# Board2.net
KiCad netlist of a schematic drawn in EasyEDA Pro
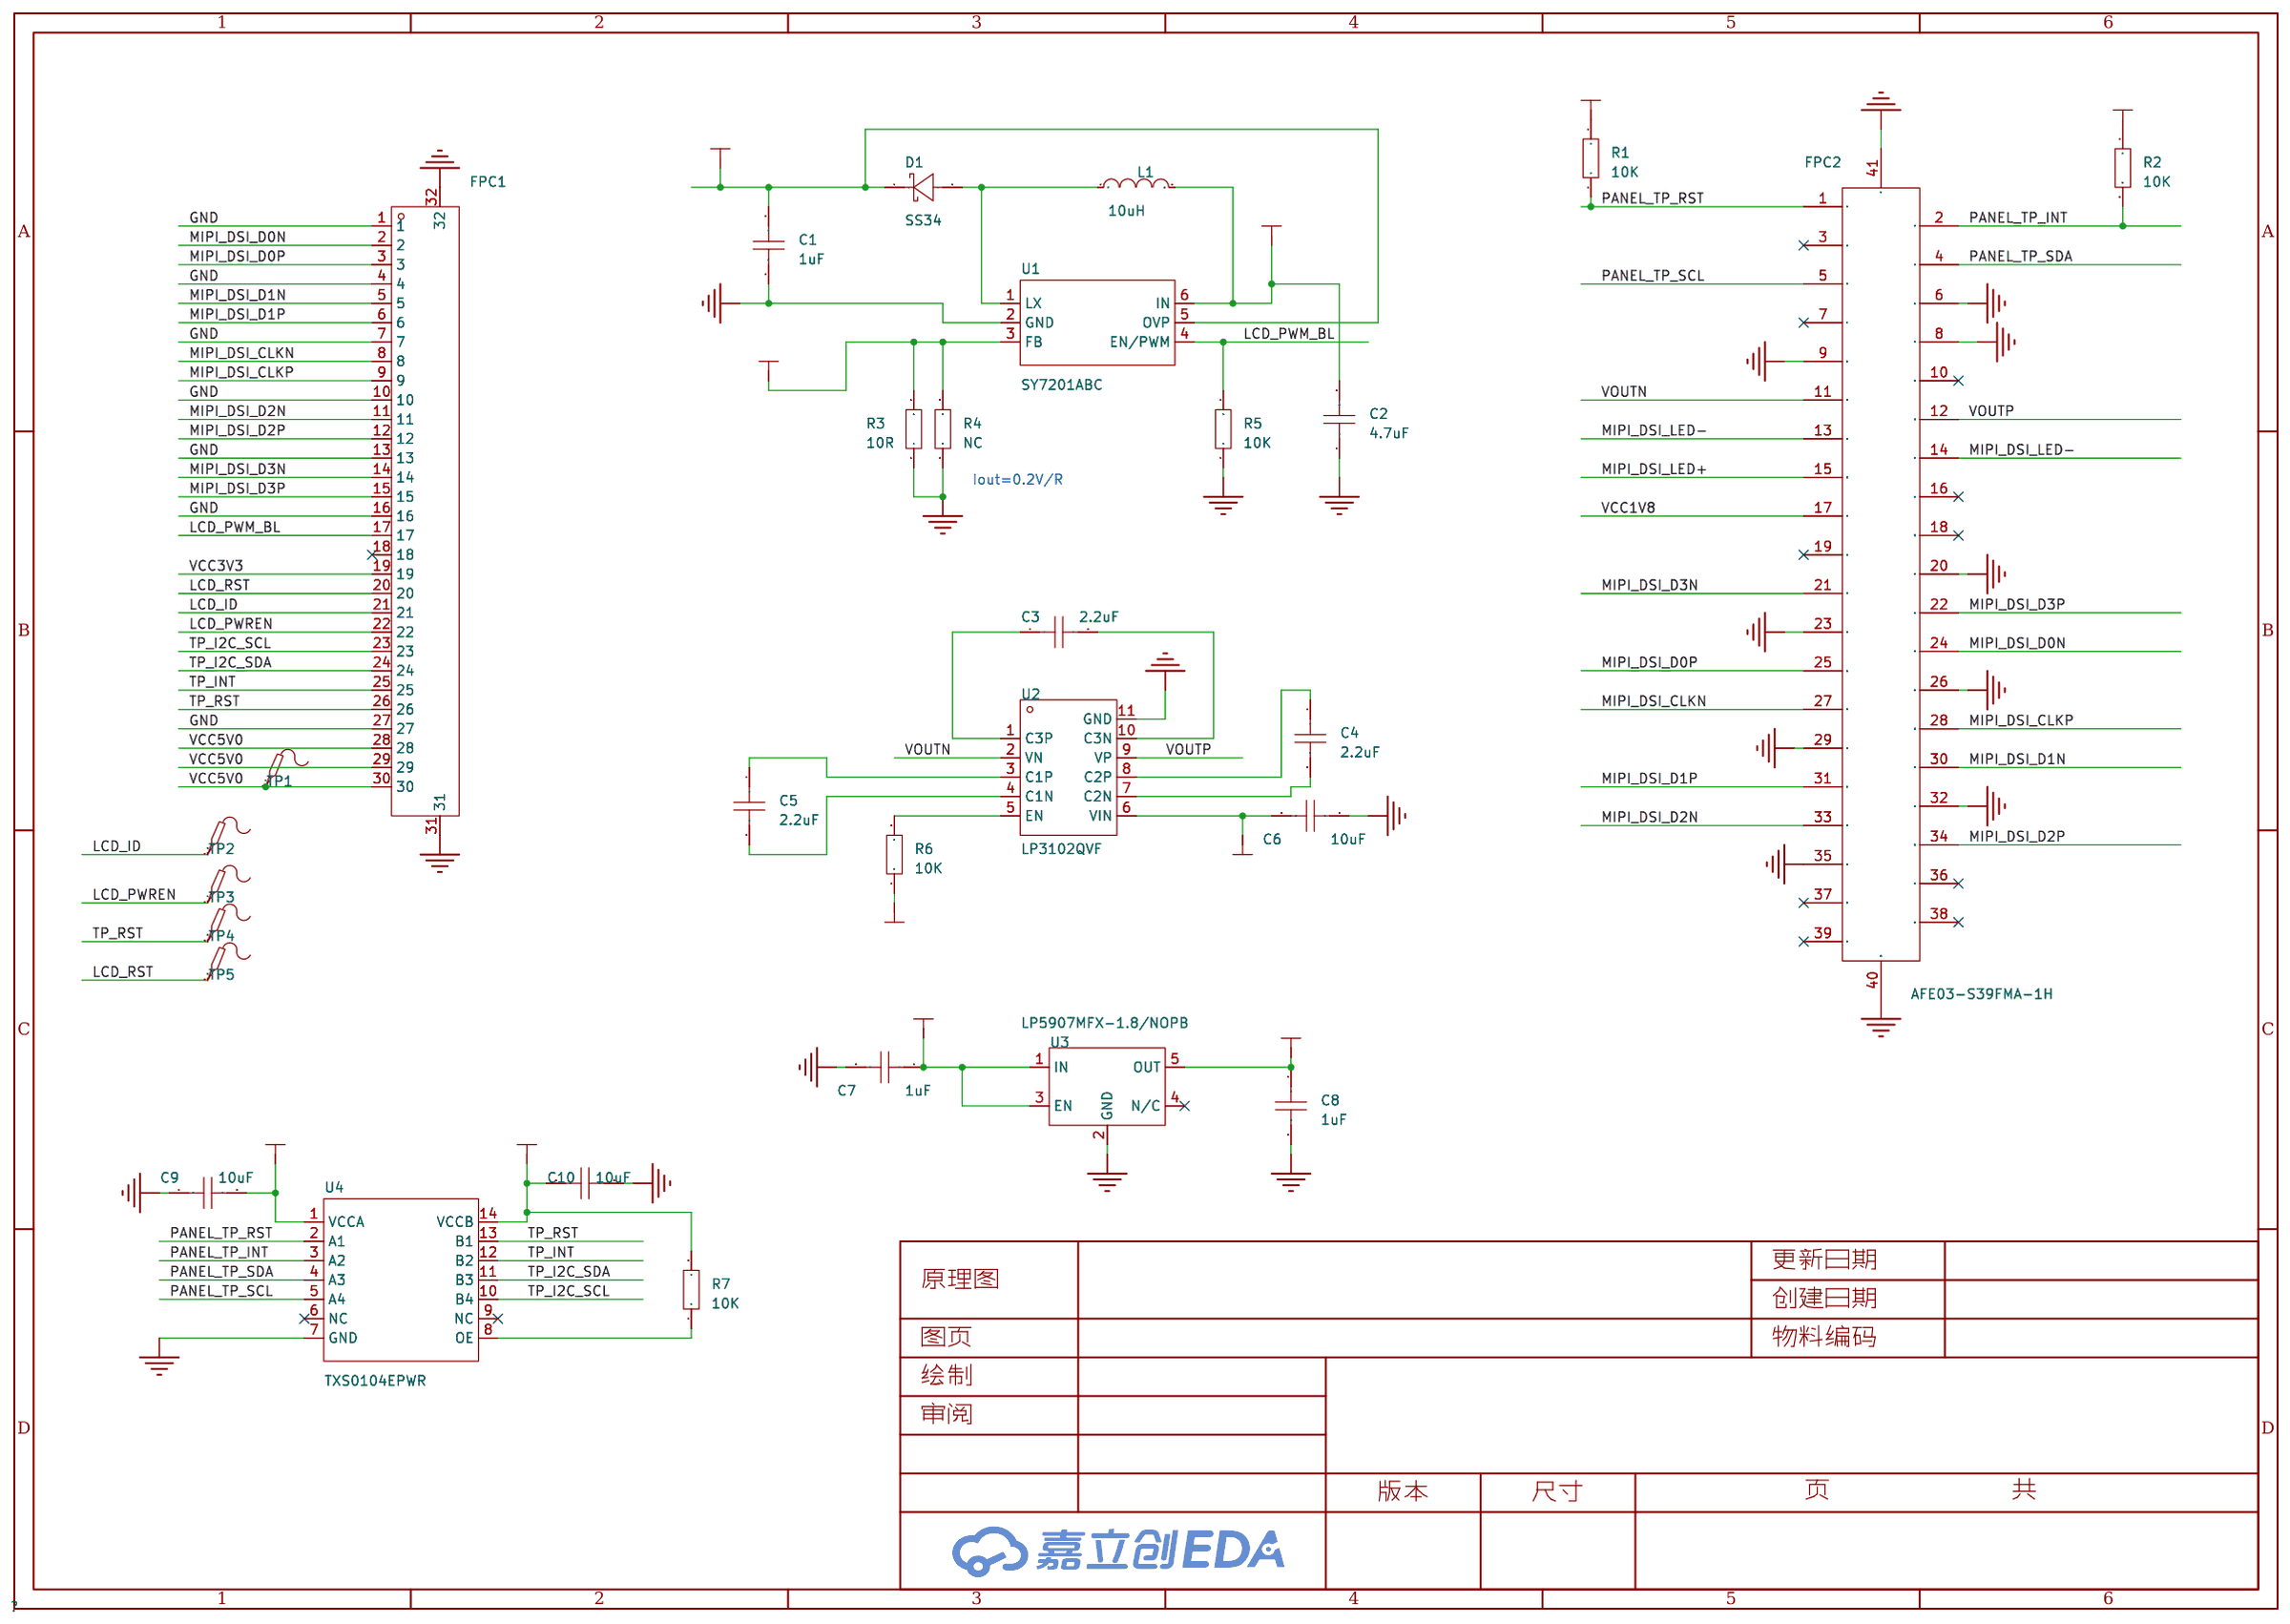
[diagram p0: schematic sheet]

(export (version "E")
  (design (tool "Eeschema 10.0.6"))
  (components
    (comp (ref "C1")
      (value "1uF")
      (footprint "easyedapro:C0603")
      (libsource (lib "easyedapro") (part "CapAcitance"))
    )
    (comp (ref "C2")
      (value "4.7uF")
      (footprint "easyedapro:C0603")
      (libsource (lib "easyedapro") (part "CapAcitance"))
    )
    (comp (ref "C3")
      (value "2.2uF")
      (footprint "easyedapro:C0603")
      (libsource (lib "easyedapro") (part "CapAcitance"))
    )
    (comp (ref "C4")
      (value "2.2uF")
      (footprint "easyedapro:C0603")
      (libsource (lib "easyedapro") (part "CapAcitance"))
    )
    (comp (ref "C5")
      (value "2.2uF")
      (footprint "easyedapro:C0603")
      (libsource (lib "easyedapro") (part "CapAcitance"))
    )
    (comp (ref "C6")
      (value "10uF")
      (footprint "easyedapro:C0603")
      (libsource (lib "easyedapro") (part "CapAcitance"))
    )
    (comp (ref "C7")
      (value "1uF")
      (footprint "easyedapro:C0603")
      (libsource (lib "easyedapro") (part "CapAcitance"))
    )
    (comp (ref "C8")
      (value "1uF")
      (footprint "easyedapro:C0603")
      (libsource (lib "easyedapro") (part "CapAcitance"))
    )
    (comp (ref "C9")
      (value "10uF")
      (footprint "easyedapro:C0603")
      (libsource (lib "easyedapro") (part "CapAcitance"))
    )
    (comp (ref "C10")
      (value "10uF")
      (footprint "easyedapro:C0603")
      (libsource (lib "easyedapro") (part "CapAcitance"))
    )
    (comp (ref "D1")
      (value "SS34")
      (footprint "easyedapro:SMA_L4.2-W2.7-LS5.0-RD")
      (description "二极管配置:-;正向压降(Vf):550mV@3A;直流反向耐压(Vr):40V;整流电流:3A;")
      (fields (field (name "Manufacturer") "JSMSEMI(杰盛微)"))
      (libsource (lib "easyedapro") (part "SS34_C2837271"))
    )
    (comp (ref "FPC1")
      (value "FPC-05F-30PH20")
      (footprint "easyedapro:FPC-SMD_30P-P0.50_XUNPU_FPC-05F-30PH20")
      (description "锁定特性:翻盖式;触点类型:卧贴;触点数量:30P;间距:0.5mm;安装方式:下接;工作温度:-25°C~+85°C;")
      (fields (field (name "Manufacturer") "XUNPU(讯普)"))
      (libsource (lib "easyedapro") (part "FPC-05F-30PH20"))
    )
    (comp (ref "FPC2")
      (value "AFE03-S39FMA-1H")
      (footprint "easyedapro:FPC-SMD_P0.30-39P_FGS-XJ-H1.0")
      (description "锁定特性:翻盖式;触点类型:下接;触点数量:39P;间距:0.3mm;安装方式:卧贴;")
      (fields (field (name "Manufacturer") "JS(钜硕电子)"))
      (libsource (lib "easyedapro") (part "AFE03-S39FMA-1H"))
    )
    (comp (ref "L1")
      (value "10uH")
      (footprint "easyedapro:L0603")
      (description "电感值:10uH;精度:±20%;额定电流:50mA;饱和电流(Isat):50mA;直流电阻(DCR):1.17Ω;")
      (fields (field (name "Manufacturer Part") "LQM18FN100M00D") (field (name "Manufacturer") "muRata(村田)"))
      (libsource (lib "easyedapro") (part "LQM18FN100M00D"))
    )
    (comp (ref "R1") (value "10K") (footprint "easyedapro:R0603") (libsource (lib "easyedapro") (part "电阻")))
    (comp (ref "R2") (value "10K") (footprint "easyedapro:R0603") (libsource (lib "easyedapro") (part "电阻")))
    (comp (ref "R3") (value "10R") (footprint "easyedapro:R0603") (libsource (lib "easyedapro") (part "电阻")))
    (comp (ref "R4") (value "NC") (footprint "easyedapro:R0603") (libsource (lib "easyedapro") (part "电阻")))
    (comp (ref "R5") (value "10K") (footprint "easyedapro:R0603") (libsource (lib "easyedapro") (part "电阻")))
    (comp (ref "R6") (value "10K") (footprint "easyedapro:R0603") (libsource (lib "easyedapro") (part "电阻")))
    (comp (ref "R7") (value "10K") (footprint "easyedapro:R0603") (libsource (lib "easyedapro") (part "电阻")))
    (comp (ref "TP1")
      (value "~")
      (footprint "easyedapro:Test-Point-0.5mm")
      (description "Test Point 测试点")
      (libsource (lib "easyedapro") (part "Test-Point"))
    )
    (comp (ref "TP2")
      (value "~")
      (footprint "easyedapro:Test-Point-0.5mm")
      (description "Test Point 测试点")
      (libsource (lib "easyedapro") (part "Test-Point"))
    )
    (comp (ref "TP3")
      (value "~")
      (footprint "easyedapro:Test-Point-0.5mm")
      (description "Test Point 测试点")
      (libsource (lib "easyedapro") (part "Test-Point"))
    )
    (comp (ref "TP4")
      (value "~")
      (footprint "easyedapro:Test-Point-0.5mm")
      (description "Test Point 测试点")
      (libsource (lib "easyedapro") (part "Test-Point"))
    )
    (comp (ref "TP5")
      (value "~")
      (footprint "easyedapro:Test-Point-0.5mm")
      (description "Test Point 测试点")
      (libsource (lib "easyedapro") (part "Test-Point"))
    )
    (comp (ref "U1")
      (value "SY7201ABC")
      (footprint "easyedapro:SOT-23-6_L2.9-W1.6-P0.95-LS2.8-BR")
      (description "类型:DC-DC;工作电压(DC):2.5V~30V;开关频率:1MHz;通道数:-;输出电压:-;输出电流:-;调光:PWM;拓扑结构:升压;")
      (fields (field (name "Manufacturer") "Silergy(矽力杰)"))
      (libsource (lib "easyedapro") (part "SY7201ABC"))
    )
    (comp (ref "U2")
      (value "LP3102QVF")
      (footprint "easyedapro:TDFN-10_L3.0-W3.0-P0.50-BL-EP")
      (fields (field (name "Manufacturer") "LOWPOWER(微源半导体)"))
      (libsource (lib "easyedapro") (part "LP3102QVF"))
    )
    (comp (ref "U3")
      (value "LP5907MFX-1.8/NOPB")
      (footprint "easyedapro:SOT-23-5_L3.0-W1.7-P0.95-LS2.8-BR")
      (description "输出类型:固定;工作电压:5.5V;输出电压:1.8V;输出电流:250mA;电源纹波抑制比(PSRR):82dB@(1kHz);输出极性:正极;")
      (fields (field (name "Manufacturer") "TI(德州仪器)"))
      (libsource (lib "easyedapro") (part "LP5907MFX-1.8/NOPB"))
    )
    (comp (ref "U4")
      (value "TXS0104EPWR")
      (footprint "easyedapro:TSSOP-14_L5.0-W4.4-P0.65-LS6.4-BL")
      (description "数据速率:24Mbps;工作电压(VCCA):1.65V~3.6V;工作电压(VCCB):2.3V~5.5V;元件数:1;每个电路通道数:4;")
      (fields (field (name "Manufacturer") "TI(德州仪器)"))
      (libsource (lib "easyedapro") (part "TXS0104EPWR"))
    )
  )
  (nets
    (net (code "1") (name "/LCD_ID") (class "Default")
      (node (ref "FPC1") (pin "21") (pinfunction "21_21") (pintype "unspecified"))
      (node (ref "TP2") (pin "1") (pinfunction "1_1") (pintype "input"))
    )
    (net (code "2") (name "/LCD_PWM_BL") (class "Default")
      (node (ref "FPC1") (pin "17") (pinfunction "17_17") (pintype "unspecified"))
      (node (ref "R5") (pin "2") (pinfunction "2_2") (pintype "input"))
      (node (ref "U1") (pin "4") (pinfunction "EN/PWM_4") (pintype "unspecified"))
    )
    (net (code "3") (name "/LCD_PWREN") (class "Default")
      (node (ref "FPC1") (pin "22") (pinfunction "22_22") (pintype "unspecified"))
      (node (ref "TP3") (pin "1") (pinfunction "1_1") (pintype "input"))
    )
    (net (code "4") (name "/LCD_RST") (class "Default")
      (node (ref "FPC1") (pin "20") (pinfunction "20_20") (pintype "unspecified"))
      (node (ref "TP5") (pin "1") (pinfunction "1_1") (pintype "input"))
    )
    (net (code "5") (name "/MIPI_DSI_CLKN") (class "Default")
      (node (ref "FPC1") (pin "8") (pinfunction "8_8") (pintype "unspecified"))
      (node (ref "FPC2") (pin "27") (pinfunction "27_27") (pintype "unspecified"))
    )
    (net (code "6") (name "/MIPI_DSI_CLKP") (class "Default")
      (node (ref "FPC1") (pin "9") (pinfunction "9_9") (pintype "unspecified"))
      (node (ref "FPC2") (pin "28") (pinfunction "28_28") (pintype "unspecified"))
    )
    (net (code "7") (name "/MIPI_DSI_D0N") (class "Default")
      (node (ref "FPC1") (pin "2") (pinfunction "2_2") (pintype "unspecified"))
      (node (ref "FPC2") (pin "24") (pinfunction "24_24") (pintype "unspecified"))
    )
    (net (code "8") (name "/MIPI_DSI_D0P") (class "Default")
      (node (ref "FPC1") (pin "3") (pinfunction "3_3") (pintype "unspecified"))
      (node (ref "FPC2") (pin "25") (pinfunction "25_25") (pintype "unspecified"))
    )
    (net (code "9") (name "/MIPI_DSI_D1N") (class "Default")
      (node (ref "FPC1") (pin "5") (pinfunction "5_5") (pintype "unspecified"))
      (node (ref "FPC2") (pin "30") (pinfunction "30_30") (pintype "unspecified"))
    )
    (net (code "10") (name "/MIPI_DSI_D1P") (class "Default")
      (node (ref "FPC1") (pin "6") (pinfunction "6_6") (pintype "unspecified"))
      (node (ref "FPC2") (pin "31") (pinfunction "31_31") (pintype "unspecified"))
    )
    (net (code "11") (name "/MIPI_DSI_D2N") (class "Default")
      (node (ref "FPC1") (pin "11") (pinfunction "11_11") (pintype "unspecified"))
      (node (ref "FPC2") (pin "33") (pinfunction "33_33") (pintype "unspecified"))
    )
    (net (code "12") (name "/MIPI_DSI_D2P") (class "Default")
      (node (ref "FPC1") (pin "12") (pinfunction "12_12") (pintype "unspecified"))
      (node (ref "FPC2") (pin "34") (pinfunction "34_34") (pintype "unspecified"))
    )
    (net (code "13") (name "/MIPI_DSI_D3N") (class "Default")
      (node (ref "FPC1") (pin "14") (pinfunction "14_14") (pintype "unspecified"))
      (node (ref "FPC2") (pin "21") (pinfunction "21_21") (pintype "unspecified"))
    )
    (net (code "14") (name "/MIPI_DSI_D3P") (class "Default")
      (node (ref "FPC1") (pin "15") (pinfunction "15_15") (pintype "unspecified"))
      (node (ref "FPC2") (pin "22") (pinfunction "22_22") (pintype "unspecified"))
    )
    (net (code "15") (name "/PANEL_TP_INT") (class "Default")
      (node (ref "FPC2") (pin "2") (pinfunction "2_2") (pintype "unspecified"))
      (node (ref "R2") (pin "2") (pinfunction "2_2") (pintype "input"))
      (node (ref "U4") (pin "3") (pinfunction "A2_3") (pintype "unspecified"))
    )
    (net (code "16") (name "/PANEL_TP_RST") (class "Default")
      (node (ref "FPC2") (pin "1") (pinfunction "1_1") (pintype "unspecified"))
      (node (ref "R1") (pin "2") (pinfunction "2_2") (pintype "input"))
      (node (ref "U4") (pin "2") (pinfunction "A1_2") (pintype "unspecified"))
    )
    (net (code "17") (name "/PANEL_TP_SCL") (class "Default")
      (node (ref "FPC2") (pin "5") (pinfunction "5_5") (pintype "unspecified"))
      (node (ref "U4") (pin "5") (pinfunction "A4_5") (pintype "unspecified"))
    )
    (net (code "18") (name "/PANEL_TP_SDA") (class "Default")
      (node (ref "FPC2") (pin "4") (pinfunction "4_4") (pintype "unspecified"))
      (node (ref "U4") (pin "4") (pinfunction "A3_4") (pintype "unspecified"))
    )
    (net (code "19") (name "/TP_I2C_SCL") (class "Default")
      (node (ref "FPC1") (pin "23") (pinfunction "23_23") (pintype "unspecified"))
      (node (ref "U4") (pin "10") (pinfunction "B4_10") (pintype "unspecified"))
    )
    (net (code "20") (name "/TP_I2C_SDA") (class "Default")
      (node (ref "FPC1") (pin "24") (pinfunction "24_24") (pintype "unspecified"))
      (node (ref "U4") (pin "11") (pinfunction "B3_11") (pintype "unspecified"))
    )
    (net (code "21") (name "/TP_INT") (class "Default")
      (node (ref "FPC1") (pin "25") (pinfunction "25_25") (pintype "unspecified"))
      (node (ref "U4") (pin "12") (pinfunction "B2_12") (pintype "unspecified"))
    )
    (net (code "22") (name "/TP_RST") (class "Default")
      (node (ref "FPC1") (pin "26") (pinfunction "26_26") (pintype "unspecified"))
      (node (ref "TP4") (pin "1") (pinfunction "1_1") (pintype "input"))
      (node (ref "U4") (pin "13") (pinfunction "B1_13") (pintype "unspecified"))
    )
    (net (code "23") (name "/VOUTN") (class "Default")
      (node (ref "FPC2") (pin "11") (pinfunction "11_11") (pintype "unspecified"))
      (node (ref "U2") (pin "2") (pinfunction "VN_2") (pintype "unspecified"))
    )
    (net (code "24") (name "/VOUTP") (class "Default")
      (node (ref "FPC2") (pin "12") (pinfunction "12_12") (pintype "unspecified"))
      (node (ref "U2") (pin "9") (pinfunction "VP_9") (pintype "unspecified"))
    )
    (net (code "25") (name "GND") (class "Default")
      (node (ref "C1") (pin "1") (pinfunction "1_1") (pintype "input"))
      (node (ref "C10") (pin "1") (pinfunction "1_1") (pintype "input"))
      (node (ref "C2") (pin "1") (pinfunction "1_1") (pintype "input"))
      (node (ref "C6") (pin "1") (pinfunction "1_1") (pintype "input"))
      (node (ref "C7") (pin "2") (pinfunction "2_2") (pintype "input"))
      (node (ref "C8") (pin "2") (pinfunction "2_2") (pintype "input"))
      (node (ref "C9") (pin "1") (pinfunction "1_1") (pintype "input"))
      (node (ref "FPC1") (pin "1") (pinfunction "1_1") (pintype "unspecified"))
      (node (ref "FPC1") (pin "10") (pinfunction "10_10") (pintype "unspecified"))
      (node (ref "FPC1") (pin "13") (pinfunction "13_13") (pintype "unspecified"))
      (node (ref "FPC1") (pin "16") (pinfunction "16_16") (pintype "unspecified"))
      (node (ref "FPC1") (pin "27") (pinfunction "27_27") (pintype "unspecified"))
      (node (ref "FPC1") (pin "31") (pinfunction "31_31") (pintype "unspecified"))
      (node (ref "FPC1") (pin "32") (pinfunction "32_32") (pintype "unspecified"))
      (node (ref "FPC1") (pin "4") (pinfunction "4_4") (pintype "unspecified"))
      (node (ref "FPC1") (pin "7") (pinfunction "7_7") (pintype "unspecified"))
      (node (ref "FPC2") (pin "20") (pinfunction "20_20") (pintype "unspecified"))
      (node (ref "FPC2") (pin "23") (pinfunction "23_23") (pintype "unspecified"))
      (node (ref "FPC2") (pin "26") (pinfunction "26_26") (pintype "unspecified"))
      (node (ref "FPC2") (pin "29") (pinfunction "29_29") (pintype "unspecified"))
      (node (ref "FPC2") (pin "32") (pinfunction "32_32") (pintype "unspecified"))
      (node (ref "FPC2") (pin "35") (pinfunction "35_35") (pintype "unspecified"))
      (node (ref "FPC2") (pin "40") (pinfunction "40_40") (pintype "unspecified"))
      (node (ref "FPC2") (pin "41") (pinfunction "41_41") (pintype "unspecified"))
      (node (ref "FPC2") (pin "6") (pinfunction "6_6") (pintype "unspecified"))
      (node (ref "FPC2") (pin "8") (pinfunction "8_8") (pintype "unspecified"))
      (node (ref "FPC2") (pin "9") (pinfunction "9_9") (pintype "unspecified"))
      (node (ref "R3") (pin "1") (pinfunction "1_1") (pintype "input"))
      (node (ref "R4") (pin "1") (pinfunction "1_1") (pintype "input"))
      (node (ref "R5") (pin "1") (pinfunction "1_1") (pintype "input"))
      (node (ref "U1") (pin "2") (pinfunction "GND_2") (pintype "unspecified"))
      (node (ref "U2") (pin "11") (pinfunction "GND_11") (pintype "unspecified"))
      (node (ref "U3") (pin "2") (pinfunction "GND_2") (pintype "unspecified"))
      (node (ref "U4") (pin "7") (pinfunction "GND_7") (pintype "unspecified"))
    )
    (net (code "26") (name "MIPI_DSI_LED+") (class "Default")
      (node (ref "C1") (pin "2") (pinfunction "2_2") (pintype "input"))
      (node (ref "D1") (pin "1") (pinfunction "K_1") (pintype "unspecified"))
      (node (ref "FPC2") (pin "15") (pinfunction "15_15") (pintype "unspecified"))
      (node (ref "U1") (pin "5") (pinfunction "OVP_5") (pintype "unspecified"))
    )
    (net (code "27") (name "MIPI_DSI_LED-") (class "Default")
      (node (ref "FPC2") (pin "13") (pinfunction "13_13") (pintype "unspecified"))
      (node (ref "FPC2") (pin "14") (pinfunction "14_14") (pintype "unspecified"))
      (node (ref "R3") (pin "2") (pinfunction "2_2") (pintype "input"))
      (node (ref "R4") (pin "2") (pinfunction "2_2") (pintype "input"))
      (node (ref "U1") (pin "3") (pinfunction "FB_3") (pintype "unspecified"))
    )
    (net (code "28") (name "Net-(D1-A)") (class "Default")
      (node (ref "D1") (pin "2") (pinfunction "A_2") (pintype "unspecified"))
      (node (ref "L1") (pin "1") (pinfunction "1_1") (pintype "unspecified"))
      (node (ref "U1") (pin "1") (pinfunction "LX_1") (pintype "unspecified"))
    )
    (net (code "29") (name "Net-(U2-C1N)") (class "Default")
      (node (ref "C5") (pin "2") (pinfunction "2_2") (pintype "input"))
      (node (ref "U2") (pin "4") (pinfunction "C1N_4") (pintype "unspecified"))
    )
    (net (code "30") (name "Net-(U2-C1P)") (class "Default")
      (node (ref "C5") (pin "1") (pinfunction "1_1") (pintype "input"))
      (node (ref "U2") (pin "3") (pinfunction "C1P_3") (pintype "unspecified"))
    )
    (net (code "31") (name "Net-(U2-C2N)") (class "Default")
      (node (ref "C4") (pin "2") (pinfunction "2_2") (pintype "input"))
      (node (ref "U2") (pin "7") (pinfunction "C2N_7") (pintype "unspecified"))
    )
    (net (code "32") (name "Net-(U2-C2P)") (class "Default")
      (node (ref "C4") (pin "1") (pinfunction "1_1") (pintype "input"))
      (node (ref "U2") (pin "8") (pinfunction "C2P_8") (pintype "unspecified"))
    )
    (net (code "33") (name "Net-(U2-C3N)") (class "Default")
      (node (ref "C3") (pin "2") (pinfunction "2_2") (pintype "input"))
      (node (ref "U2") (pin "10") (pinfunction "C3N_10") (pintype "unspecified"))
    )
    (net (code "34") (name "Net-(U2-C3P)") (class "Default")
      (node (ref "C3") (pin "1") (pinfunction "1_1") (pintype "input"))
      (node (ref "U2") (pin "1") (pinfunction "C3P_1") (pintype "unspecified"))
    )
    (net (code "35") (name "Net-(U2-EN)") (class "Default")
      (node (ref "R6") (pin "2") (pinfunction "2_2") (pintype "input"))
      (node (ref "U2") (pin "5") (pinfunction "EN_5") (pintype "unspecified"))
    )
    (net (code "36") (name "Net-(U4-OE)") (class "Default")
      (node (ref "R7") (pin "1") (pinfunction "1_1") (pintype "input"))
      (node (ref "U4") (pin "8") (pinfunction "OE_8") (pintype "unspecified"))
    )
    (net (code "37") (name "VCC1V8") (class "Default")
      (node (ref "C8") (pin "1") (pinfunction "1_1") (pintype "input"))
      (node (ref "C9") (pin "2") (pinfunction "2_2") (pintype "input"))
      (node (ref "FPC2") (pin "17") (pinfunction "17_17") (pintype "unspecified"))
      (node (ref "R1") (pin "1") (pinfunction "1_1") (pintype "input"))
      (node (ref "R2") (pin "1") (pinfunction "1_1") (pintype "input"))
      (node (ref "U3") (pin "5") (pinfunction "OUT_5") (pintype "unspecified"))
      (node (ref "U4") (pin "1") (pinfunction "VCCA_1") (pintype "unspecified"))
    )
    (net (code "38") (name "VCC3V3") (class "Default")
      (node (ref "C10") (pin "2") (pinfunction "2_2") (pintype "input"))
      (node (ref "C6") (pin "2") (pinfunction "2_2") (pintype "input"))
      (node (ref "FPC1") (pin "19") (pinfunction "19_19") (pintype "unspecified"))
      (node (ref "R6") (pin "1") (pinfunction "1_1") (pintype "input"))
      (node (ref "R7") (pin "2") (pinfunction "2_2") (pintype "input"))
      (node (ref "U2") (pin "6") (pinfunction "VIN_6") (pintype "unspecified"))
      (node (ref "U4") (pin "14") (pinfunction "VCCB_14") (pintype "unspecified"))
    )
    (net (code "39") (name "VCC5V0") (class "Default")
      (node (ref "C2") (pin "2") (pinfunction "2_2") (pintype "input"))
      (node (ref "C7") (pin "1") (pinfunction "1_1") (pintype "input"))
      (node (ref "FPC1") (pin "28") (pinfunction "28_28") (pintype "unspecified"))
      (node (ref "FPC1") (pin "29") (pinfunction "29_29") (pintype "unspecified"))
      (node (ref "FPC1") (pin "30") (pinfunction "30_30") (pintype "unspecified"))
      (node (ref "L1") (pin "2") (pinfunction "2_2") (pintype "unspecified"))
      (node (ref "TP1") (pin "1") (pinfunction "1_1") (pintype "input"))
      (node (ref "U1") (pin "6") (pinfunction "IN_6") (pintype "unspecified"))
      (node (ref "U3") (pin "1") (pinfunction "IN_1") (pintype "unspecified"))
      (node (ref "U3") (pin "3") (pinfunction "EN_3") (pintype "unspecified"))
    )
    (net (code "40") (name "unconnected-(FPC1-Pad18)") (class "Default")
      (node (ref "FPC1") (pin "18") (pinfunction "18_18") (pintype "unspecified+no_connect"))
    )
    (net (code "41") (name "unconnected-(FPC2-Pad3)") (class "Default")
      (node (ref "FPC2") (pin "3") (pinfunction "3_3") (pintype "unspecified+no_connect"))
    )
    (net (code "42") (name "unconnected-(FPC2-Pad7)") (class "Default")
      (node (ref "FPC2") (pin "7") (pinfunction "7_7") (pintype "unspecified+no_connect"))
    )
    (net (code "43") (name "unconnected-(FPC2-Pad10)") (class "Default")
      (node (ref "FPC2") (pin "10") (pinfunction "10_10") (pintype "unspecified+no_connect"))
    )
    (net (code "44") (name "unconnected-(FPC2-Pad16)") (class "Default")
      (node (ref "FPC2") (pin "16") (pinfunction "16_16") (pintype "unspecified+no_connect"))
    )
    (net (code "45") (name "unconnected-(FPC2-Pad18)") (class "Default")
      (node (ref "FPC2") (pin "18") (pinfunction "18_18") (pintype "unspecified+no_connect"))
    )
    (net (code "46") (name "unconnected-(FPC2-Pad19)") (class "Default")
      (node (ref "FPC2") (pin "19") (pinfunction "19_19") (pintype "unspecified+no_connect"))
    )
    (net (code "47") (name "unconnected-(FPC2-Pad36)") (class "Default")
      (node (ref "FPC2") (pin "36") (pinfunction "36_36") (pintype "unspecified+no_connect"))
    )
    (net (code "48") (name "unconnected-(FPC2-Pad37)") (class "Default")
      (node (ref "FPC2") (pin "37") (pinfunction "37_37") (pintype "unspecified+no_connect"))
    )
    (net (code "49") (name "unconnected-(FPC2-Pad38)") (class "Default")
      (node (ref "FPC2") (pin "38") (pinfunction "38_38") (pintype "unspecified+no_connect"))
    )
    (net (code "50") (name "unconnected-(FPC2-Pad39)") (class "Default")
      (node (ref "FPC2") (pin "39") (pinfunction "39_39") (pintype "unspecified+no_connect"))
    )
    (net (code "51") (name "unconnected-(U3-N{slash}C-Pad4)") (class "Default")
      (node (ref "U3") (pin "4") (pinfunction "N/C_4") (pintype "unspecified+no_connect"))
    )
    (net (code "52") (name "unconnected-(U4-NC-Pad6)") (class "Default")
      (node (ref "U4") (pin "6") (pinfunction "NC_6") (pintype "unspecified+no_connect"))
    )
    (net (code "53") (name "unconnected-(U4-NC-Pad9)") (class "Default")
      (node (ref "U4") (pin "9") (pinfunction "NC_9") (pintype "unspecified+no_connect"))
    )
  )
)
